# TDA7000.net
KiCad netlist of a schematic drawn in Altium Designer
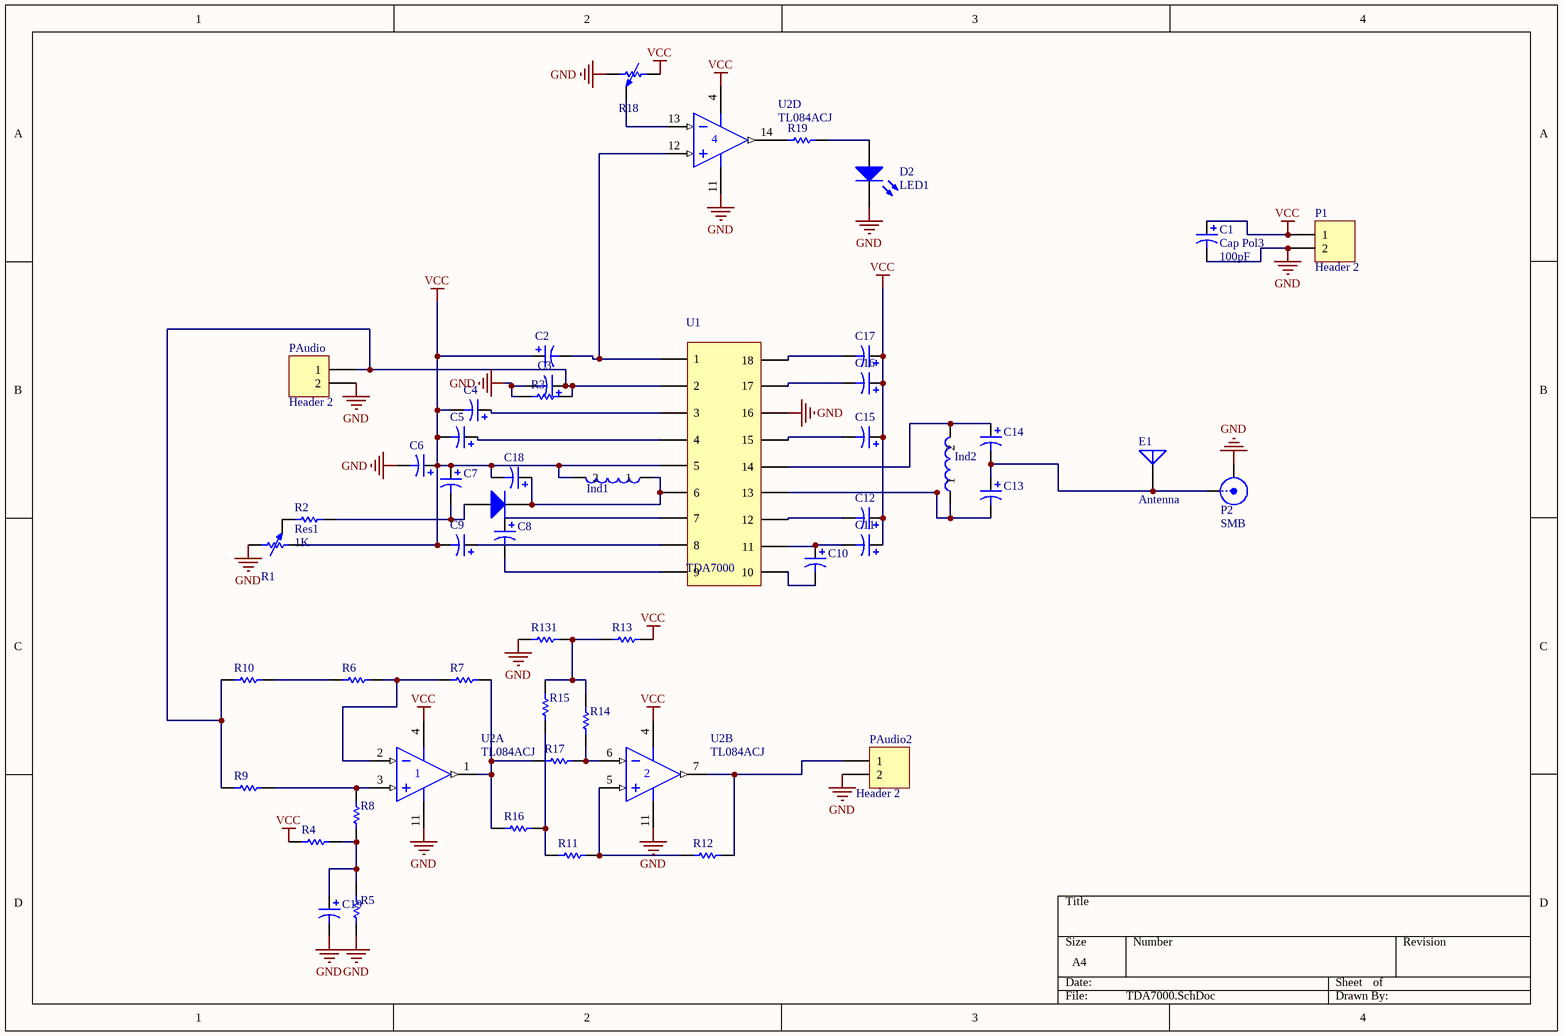
[diagram p0: TDA7000.SchDoc]

(export (version "E")
  (design (tool "Eeschema 10.0.6"))
  (components
    (comp (ref "C1")
      (value "Cap Pol3")
      (footprint "C0805")
      (description "Polarized Capacitor (Surface Mount)")
      (fields (field (name "ALTIUM_VALUE") "100pF") (field (name "PUBLISHER") "Altium Limited"))
      (libsource (lib "Miscellaneous Devices") (part "Cap Pol3"))
    )
    (comp (ref "C2")
      (value "Cap Pol3")
      (footprint "C0805")
      (description "Polarized Capacitor (Surface Mount)")
      (fields (field (name "PUBLISHER") "Altium Limited"))
      (libsource (lib "Miscellaneous Devices") (part "Cap Pol3"))
    )
    (comp (ref "C3")
      (value "Cap Pol3")
      (footprint "C0805")
      (description "Polarized Capacitor (Surface Mount)")
      (fields (field (name "PUBLISHER") "Altium Limited"))
      (libsource (lib "Miscellaneous Devices") (part "Cap Pol3"))
    )
    (comp (ref "C4")
      (value "Cap Pol3")
      (footprint "C0805")
      (description "Polarized Capacitor (Surface Mount)")
      (fields (field (name "PUBLISHER") "Altium Limited"))
      (libsource (lib "Miscellaneous Devices") (part "Cap Pol3"))
    )
    (comp (ref "C5")
      (value "Cap Pol3")
      (footprint "C0805")
      (description "Polarized Capacitor (Surface Mount)")
      (fields (field (name "PUBLISHER") "Altium Limited"))
      (libsource (lib "Miscellaneous Devices") (part "Cap Pol3"))
    )
    (comp (ref "C6")
      (value "Cap Pol3")
      (footprint "C0805")
      (description "Polarized Capacitor (Surface Mount)")
      (fields (field (name "PUBLISHER") "Altium Limited"))
      (libsource (lib "Miscellaneous Devices") (part "Cap Pol3"))
    )
    (comp (ref "C7")
      (value "Cap Pol3")
      (footprint "C0805")
      (description "Polarized Capacitor (Surface Mount)")
      (fields (field (name "PUBLISHER") "Altium Limited"))
      (libsource (lib "Miscellaneous Devices") (part "Cap Pol3"))
    )
    (comp (ref "C8")
      (value "Cap Pol3")
      (footprint "C0805")
      (description "Polarized Capacitor (Surface Mount)")
      (fields (field (name "PUBLISHER") "Altium Limited"))
      (libsource (lib "Miscellaneous Devices") (part "Cap Pol3"))
    )
    (comp (ref "C9")
      (value "Cap Pol3")
      (footprint "C0805")
      (description "Polarized Capacitor (Surface Mount)")
      (fields (field (name "PUBLISHER") "Altium Limited"))
      (libsource (lib "Miscellaneous Devices") (part "Cap Pol3"))
    )
    (comp (ref "C10")
      (value "Cap Pol3")
      (footprint "C0805")
      (description "Polarized Capacitor (Surface Mount)")
      (fields (field (name "PUBLISHER") "Altium Limited"))
      (libsource (lib "Miscellaneous Devices") (part "Cap Pol3"))
    )
    (comp (ref "C11")
      (value "Cap Pol3")
      (footprint "C0805")
      (description "Polarized Capacitor (Surface Mount)")
      (fields (field (name "PUBLISHER") "Altium Limited"))
      (libsource (lib "Miscellaneous Devices") (part "Cap Pol3"))
    )
    (comp (ref "C12")
      (value "Cap Pol3")
      (footprint "C0805")
      (description "Polarized Capacitor (Surface Mount)")
      (fields (field (name "PUBLISHER") "Altium Limited"))
      (libsource (lib "Miscellaneous Devices") (part "Cap Pol3"))
    )
    (comp (ref "C13")
      (value "Cap Pol3")
      (footprint "C0805")
      (description "Polarized Capacitor (Surface Mount)")
      (fields (field (name "PUBLISHER") "Altium Limited"))
      (libsource (lib "Miscellaneous Devices") (part "Cap Pol3"))
    )
    (comp (ref "C14")
      (value "Cap Pol3")
      (footprint "C0805")
      (description "Polarized Capacitor (Surface Mount)")
      (fields (field (name "PUBLISHER") "Altium Limited"))
      (libsource (lib "Miscellaneous Devices") (part "Cap Pol3"))
    )
    (comp (ref "C15")
      (value "Cap Pol3")
      (footprint "C0805")
      (description "Polarized Capacitor (Surface Mount)")
      (fields (field (name "PUBLISHER") "Altium Limited"))
      (libsource (lib "Miscellaneous Devices") (part "Cap Pol3"))
    )
    (comp (ref "C16")
      (value "Cap Pol3")
      (footprint "C0805")
      (description "Polarized Capacitor (Surface Mount)")
      (fields (field (name "PUBLISHER") "Altium Limited"))
      (libsource (lib "Miscellaneous Devices") (part "Cap Pol3"))
    )
    (comp (ref "C17")
      (value "Cap Pol3")
      (footprint "C0805")
      (description "Polarized Capacitor (Surface Mount)")
      (fields (field (name "PUBLISHER") "Altium Limited"))
      (libsource (lib "Miscellaneous Devices") (part "Cap Pol3"))
    )
    (comp (ref "C18")
      (value "Cap Pol3")
      (footprint "C0805")
      (description "Polarized Capacitor (Surface Mount)")
      (fields (field (name "PUBLISHER") "Altium Limited"))
      (libsource (lib "Miscellaneous Devices") (part "Cap Pol3"))
    )
    (comp (ref "C19")
      (value "Cap Pol3")
      (footprint "C0805")
      (description "Polarized Capacitor (Surface Mount)")
      (fields (field (name "PUBLISHER") "Altium Limited"))
      (libsource (lib "Miscellaneous Devices") (part "Cap Pol3"))
    )
    (comp (ref "D1")
      (value "Diode 1N914")
      (footprint "DO-35")
      (description "High Conductance Fast Diode")
      (fields (field (name "PUBLISHER") "Altium Limited"))
      (libsource (lib "Miscellaneous Devices") (part "Diode 1N914"))
    )
    (comp (ref "D2")
      (value "LED1")
      (footprint "LED-1")
      (description "Typical RED GaAs LED")
      (fields (field (name "PUBLISHER") "Altium Limited"))
      (libsource (lib "Miscellaneous Devices") (part "LED1"))
    )
    (comp (ref "E1")
      (value "Antenna")
      (footprint "PIN1")
      (description "Generic Antenna")
      (fields (field (name "PUBLISHER") "Altium Limited"))
      (libsource (lib "Miscellaneous Devices") (part "Antenna"))
    )
    (comp (ref "Ind1") (value "Ind2") (footprint "Ind_3mm") (libsource (lib "epf") (part "Ind2")))
    (comp (ref "Ind2") (value "Ind2") (footprint "Ind_3mm") (libsource (lib "epf") (part "Ind2")))
    (comp (ref "P1")
      (value "Header 2")
      (footprint "HDR1X2")
      (description "Header, 2-Pin")
      (fields (field (name "PUBLISHER") "Altium Limited"))
      (libsource (lib "") (part "Header 2_1"))
    )
    (comp (ref "P2")
      (value "SMB")
      (footprint "SMB_V-RJ45")
      (description "SMB Straight Connector")
      (fields (field (name "PUBLISHER") "Altium Limited"))
      (libsource (lib "Miscellaneous Connectors") (part "SMB"))
    )
    (comp (ref "PAudio")
      (value "Header 2")
      (footprint "HDR1X2")
      (description "Header, 2-Pin")
      (fields (field (name "PUBLISHER") "Altium Limited"))
      (libsource (lib "Miscellaneous Connectors") (part "Header 2"))
    )
    (comp (ref "PAudio2")
      (value "Header 2")
      (footprint "HDR1X2")
      (description "Header, 2-Pin")
      (fields (field (name "PUBLISHER") "Altium Limited"))
      (libsource (lib "") (part "Header 2_1"))
    )
    (comp (ref "R1") (value "Pot") (footprint "Potenciometro") (libsource (lib "epf") (part "Pot")))
    (comp (ref "R2")
      (value "Res1")
      (footprint "AXIAL-0.3")
      (description "Resistor")
      (fields (field (name "ALTIUM_VALUE") "1K") (field (name "PUBLISHER") "Altium Limited"))
      (libsource (lib "Miscellaneous Devices") (part "Res1"))
    )
    (comp (ref "R3")
      (value "Res Semi")
      (footprint "2012[0805]")
      (description "Semiconductor Resistor")
      (fields (field (name "PUBLISHER") "Altium Limited"))
      (libsource (lib "Miscellaneous Devices") (part "Res Semi"))
    )
    (comp (ref "R4")
      (value "Res Semi")
      (footprint "2012[0805]")
      (description "Semiconductor Resistor")
      (fields (field (name "PUBLISHER") "Altium Limited"))
      (libsource (lib "Miscellaneous Devices") (part "Res Semi"))
    )
    (comp (ref "R5")
      (value "Res Semi")
      (footprint "2012[0805]")
      (description "Semiconductor Resistor")
      (fields (field (name "PUBLISHER") "Altium Limited"))
      (libsource (lib "Miscellaneous Devices") (part "Res Semi"))
    )
    (comp (ref "R6")
      (value "Res Semi")
      (footprint "2012[0805]")
      (description "Semiconductor Resistor")
      (fields (field (name "PUBLISHER") "Altium Limited"))
      (libsource (lib "Miscellaneous Devices") (part "Res Semi"))
    )
    (comp (ref "R7")
      (value "Res Semi")
      (footprint "2012[0805]")
      (description "Semiconductor Resistor")
      (fields (field (name "PUBLISHER") "Altium Limited"))
      (libsource (lib "Miscellaneous Devices") (part "Res Semi"))
    )
    (comp (ref "R8")
      (value "Res Semi")
      (footprint "2012[0805]")
      (description "Semiconductor Resistor")
      (fields (field (name "PUBLISHER") "Altium Limited"))
      (libsource (lib "Miscellaneous Devices") (part "Res Semi"))
    )
    (comp (ref "R9")
      (value "Res Semi")
      (footprint "2012[0805]")
      (description "Semiconductor Resistor")
      (fields (field (name "PUBLISHER") "Altium Limited"))
      (libsource (lib "Miscellaneous Devices") (part "Res Semi"))
    )
    (comp (ref "R10")
      (value "Res Semi")
      (footprint "2012[0805]")
      (description "Semiconductor Resistor")
      (fields (field (name "PUBLISHER") "Altium Limited"))
      (libsource (lib "Miscellaneous Devices") (part "Res Semi"))
    )
    (comp (ref "R11")
      (value "Res Semi")
      (footprint "2012[0805]")
      (description "Semiconductor Resistor")
      (fields (field (name "PUBLISHER") "Altium Limited"))
      (libsource (lib "Miscellaneous Devices") (part "Res Semi"))
    )
    (comp (ref "R12")
      (value "Res Semi")
      (footprint "2012[0805]")
      (description "Semiconductor Resistor")
      (fields (field (name "PUBLISHER") "Altium Limited"))
      (libsource (lib "Miscellaneous Devices") (part "Res Semi"))
    )
    (comp (ref "R13")
      (value "Res Semi")
      (footprint "2012[0805]")
      (description "Semiconductor Resistor")
      (fields (field (name "PUBLISHER") "Altium Limited"))
      (libsource (lib "Miscellaneous Devices") (part "Res Semi"))
    )
    (comp (ref "R14")
      (value "Res Semi")
      (footprint "2012[0805]")
      (description "Semiconductor Resistor")
      (fields (field (name "PUBLISHER") "Altium Limited"))
      (libsource (lib "Miscellaneous Devices") (part "Res Semi"))
    )
    (comp (ref "R15")
      (value "Res Semi")
      (footprint "2012[0805]")
      (description "Semiconductor Resistor")
      (fields (field (name "PUBLISHER") "Altium Limited"))
      (libsource (lib "Miscellaneous Devices") (part "Res Semi"))
    )
    (comp (ref "R16")
      (value "Res Semi")
      (footprint "2012[0805]")
      (description "Semiconductor Resistor")
      (fields (field (name "PUBLISHER") "Altium Limited"))
      (libsource (lib "Miscellaneous Devices") (part "Res Semi"))
    )
    (comp (ref "R17")
      (value "Res Semi")
      (footprint "2012[0805]")
      (description "Semiconductor Resistor")
      (fields (field (name "PUBLISHER") "Altium Limited"))
      (libsource (lib "Miscellaneous Devices") (part "Res Semi"))
    )
    (comp (ref "R18") (value "Pot") (footprint "Potenciometro") (libsource (lib "epf") (part "Pot")))
    (comp (ref "R19")
      (value "Res Semi")
      (footprint "2012[0805]")
      (description "Semiconductor Resistor")
      (fields (field (name "PUBLISHER") "Altium Limited"))
      (libsource (lib "Miscellaneous Devices") (part "Res Semi"))
    )
    (comp (ref "R131")
      (value "Res Semi")
      (footprint "2012[0805]")
      (description "Semiconductor Resistor")
      (fields (field (name "PUBLISHER") "Altium Limited"))
      (libsource (lib "Miscellaneous Devices") (part "Res Semi"))
    )
    (comp (ref "U1") (value "TDA7000") (footprint "TDA7000") (libsource (lib "epf") (part "TDA7000")))
    (comp (ref "U2")
      (value "TL084ACJ")
      (footprint "632-08")
      (description "JFET-Input Operational Amplifier")
      (fields (field (name "PUBLISHER") "Altium Limited"))
      (libsource (lib "Motorola Amplifier Operational Amplifier") (part "TL084ACJ"))
    )
  )
  (nets
    (net (code "1") (name "GND") (class "Default")
      (node (ref "C1") (pin "2") (pinfunction "2_2") (pintype "passive"))
      (node (ref "C19") (pin "2") (pinfunction "2_2") (pintype "passive"))
      (node (ref "C3") (pin "2") (pinfunction "2_2") (pintype "passive"))
      (node (ref "C6") (pin "2") (pinfunction "2_2") (pintype "passive"))
      (node (ref "D2") (pin "2") (pinfunction "K_2") (pintype "passive"))
      (node (ref "P1") (pin "2") (pinfunction "2_2") (pintype "passive"))
      (node (ref "P2") (pin "2") (pinfunction "Y_2") (pintype "passive"))
      (node (ref "PAudio") (pin "2") (pinfunction "2_2") (pintype "passive"))
      (node (ref "PAudio2") (pin "2") (pinfunction "2_2") (pintype "passive"))
      (node (ref "R1") (pin "1") (pinfunction "1_1") (pintype "passive"))
      (node (ref "R131") (pin "2") (pinfunction "2_2") (pintype "passive"))
      (node (ref "R18") (pin "2") (pinfunction "2_2") (pintype "passive"))
      (node (ref "R3") (pin "1") (pinfunction "1_1") (pintype "passive"))
      (node (ref "R5") (pin "1") (pinfunction "1_1") (pintype "passive"))
      (node (ref "U1") (pin "16") (pinfunction "16_16") (pintype "passive"))
      (node (ref "U2") (pin "11") (pinfunction "V-_11") (pintype "power_in"))
    )
    (net (code "2") (name "Net-(C3-Pad1)") (class "Default")
      (node (ref "C3") (pin "1") (pinfunction "1_1") (pintype "passive"))
      (node (ref "PAudio") (pin "1") (pinfunction "1_1") (pintype "passive"))
      (node (ref "R10") (pin "2") (pinfunction "2_2") (pintype "passive"))
      (node (ref "R3") (pin "2") (pinfunction "2_2") (pintype "passive"))
      (node (ref "R9") (pin "2") (pinfunction "2_2") (pintype "passive"))
      (node (ref "U1") (pin "2") (pinfunction "2_2") (pintype "passive"))
    )
    (net (code "3") (name "Net-(C4-Pad1)") (class "Default")
      (node (ref "C4") (pin "1") (pinfunction "1_1") (pintype "passive"))
      (node (ref "U1") (pin "3") (pinfunction "3_3") (pintype "passive"))
    )
    (net (code "4") (name "Net-(C5-Pad1)") (class "Default")
      (node (ref "C5") (pin "1") (pinfunction "1_1") (pintype "passive"))
      (node (ref "U1") (pin "4") (pinfunction "4_4") (pintype "passive"))
    )
    (net (code "5") (name "Net-(C8-Pad1)") (class "Default")
      (node (ref "C8") (pin "1") (pinfunction "1_1") (pintype "passive"))
      (node (ref "U1") (pin "7") (pinfunction "7_7") (pintype "passive"))
    )
    (net (code "6") (name "Net-(C8-Pad2)") (class "Default")
      (node (ref "C8") (pin "2") (pinfunction "2_2") (pintype "passive"))
      (node (ref "U1") (pin "9") (pinfunction "9_9") (pintype "passive"))
    )
    (net (code "7") (name "Net-(C9-Pad1)") (class "Default")
      (node (ref "C9") (pin "1") (pinfunction "1_1") (pintype "passive"))
      (node (ref "U1") (pin "8") (pinfunction "8_8") (pintype "passive"))
    )
    (net (code "8") (name "Net-(C10-Pad1)") (class "Default")
      (node (ref "C10") (pin "1") (pinfunction "1_1") (pintype "passive"))
      (node (ref "C11") (pin "2") (pinfunction "2_2") (pintype "passive"))
      (node (ref "U1") (pin "11") (pinfunction "11_11") (pintype "passive"))
    )
    (net (code "9") (name "Net-(C10-Pad2)") (class "Default")
      (node (ref "C10") (pin "2") (pinfunction "2_2") (pintype "passive"))
      (node (ref "U1") (pin "10") (pinfunction "10_10") (pintype "passive"))
    )
    (net (code "10") (name "Net-(C12-Pad2)") (class "Default")
      (node (ref "C12") (pin "2") (pinfunction "2_2") (pintype "passive"))
      (node (ref "U1") (pin "12") (pinfunction "12_12") (pintype "passive"))
    )
    (net (code "11") (name "Net-(C13-Pad2)") (class "Default")
      (node (ref "C13") (pin "2") (pinfunction "2_2") (pintype "passive"))
      (node (ref "Ind2") (pin "1") (pinfunction "1_1") (pintype "passive"))
      (node (ref "U1") (pin "13") (pinfunction "13_13") (pintype "passive"))
    )
    (net (code "12") (name "Net-(C14-Pad1)") (class "Default")
      (node (ref "C14") (pin "1") (pinfunction "1_1") (pintype "passive"))
      (node (ref "Ind2") (pin "2") (pinfunction "2_2") (pintype "passive"))
      (node (ref "U1") (pin "14") (pinfunction "14_14") (pintype "passive"))
    )
    (net (code "13") (name "Net-(C15-Pad2)") (class "Default")
      (node (ref "C15") (pin "2") (pinfunction "2_2") (pintype "passive"))
      (node (ref "U1") (pin "15") (pinfunction "15_15") (pintype "passive"))
    )
    (net (code "14") (name "Net-(C16-Pad2)") (class "Default")
      (node (ref "C16") (pin "2") (pinfunction "2_2") (pintype "passive"))
      (node (ref "U1") (pin "17") (pinfunction "17_17") (pintype "passive"))
    )
    (net (code "15") (name "Net-(C17-Pad2)") (class "Default")
      (node (ref "C17") (pin "2") (pinfunction "2_2") (pintype "passive"))
      (node (ref "U1") (pin "18") (pinfunction "18_18") (pintype "passive"))
    )
    (net (code "16") (name "Net-(C19-Pad1)") (class "Default")
      (node (ref "C19") (pin "1") (pinfunction "1_1") (pintype "passive"))
      (node (ref "R4") (pin "2") (pinfunction "2_2") (pintype "passive"))
      (node (ref "R5") (pin "2") (pinfunction "2_2") (pintype "passive"))
      (node (ref "R8") (pin "1") (pinfunction "1_1") (pintype "passive"))
    )
    (net (code "17") (name "Net-(D1-A)") (class "Default")
      (node (ref "C7") (pin "2") (pinfunction "2_2") (pintype "passive"))
      (node (ref "D1") (pin "1") (pinfunction "A_1") (pintype "passive"))
      (node (ref "R2") (pin "2") (pinfunction "2_2") (pintype "passive"))
    )
    (net (code "18") (name "Net-(D1-K)") (class "Default")
      (node (ref "C18") (pin "1") (pinfunction "1_1") (pintype "passive"))
      (node (ref "D1") (pin "2") (pinfunction "K_2") (pintype "passive"))
      (node (ref "Ind1") (pin "1") (pinfunction "1_1") (pintype "passive"))
      (node (ref "U1") (pin "6") (pinfunction "6_6") (pintype "passive"))
    )
    (net (code "19") (name "Net-(D2-A)") (class "Default")
      (node (ref "D2") (pin "1") (pinfunction "A_1") (pintype "passive"))
      (node (ref "R19") (pin "2") (pinfunction "2_2") (pintype "passive"))
    )
    (net (code "20") (name "Net-(E1-A)") (class "Default")
      (node (ref "C13") (pin "1") (pinfunction "1_1") (pintype "passive"))
      (node (ref "C14") (pin "2") (pinfunction "2_2") (pintype "passive"))
      (node (ref "E1") (pin "1") (pinfunction "A_1") (pintype "passive"))
      (node (ref "P2") (pin "1") (pinfunction "X_1") (pintype "passive"))
    )
    (net (code "21") (name "Net-(R1-Pad3)") (class "Default")
      (node (ref "R1") (pin "3") (pinfunction "3_3") (pintype "passive"))
      (node (ref "R2") (pin "1") (pinfunction "1_1") (pintype "passive"))
    )
    (net (code "22") (name "Net-(R10-Pad1)") (class "Default")
      (node (ref "R10") (pin "1") (pinfunction "1_1") (pintype "passive"))
      (node (ref "R6") (pin "2") (pinfunction "2_2") (pintype "passive"))
    )
    (net (code "23") (name "Net-(R11-Pad2)") (class "Default")
      (node (ref "R11") (pin "2") (pinfunction "2_2") (pintype "passive"))
      (node (ref "R15") (pin "2") (pinfunction "2_2") (pintype "passive"))
      (node (ref "R16") (pin "2") (pinfunction "2_2") (pintype "passive"))
    )
    (net (code "24") (name "Net-(R13-Pad2)") (class "Default")
      (node (ref "R13") (pin "2") (pinfunction "2_2") (pintype "passive"))
      (node (ref "R131") (pin "1") (pinfunction "1_1") (pintype "passive"))
      (node (ref "R14") (pin "1") (pinfunction "1_1") (pintype "passive"))
      (node (ref "R15") (pin "1") (pinfunction "1_1") (pintype "passive"))
    )
    (net (code "25") (name "Net-(U2A-IN+)") (class "Default")
      (node (ref "R8") (pin "2") (pinfunction "2_2") (pintype "passive"))
      (node (ref "R9") (pin "1") (pinfunction "1_1") (pintype "passive"))
      (node (ref "U2") (pin "3") (pinfunction "IN+_3") (pintype "input"))
    )
    (net (code "26") (name "Net-(U2A-IN-)") (class "Default")
      (node (ref "R6") (pin "1") (pinfunction "1_1") (pintype "passive"))
      (node (ref "R7") (pin "2") (pinfunction "2_2") (pintype "passive"))
      (node (ref "U2") (pin "2") (pinfunction "IN-_2") (pintype "input"))
    )
    (net (code "27") (name "Net-(U2A-OUT)") (class "Default")
      (node (ref "R16") (pin "1") (pinfunction "1_1") (pintype "passive"))
      (node (ref "R17") (pin "1") (pinfunction "1_1") (pintype "passive"))
      (node (ref "R7") (pin "1") (pinfunction "1_1") (pintype "passive"))
      (node (ref "U2") (pin "1") (pinfunction "OUT_1") (pintype "output"))
    )
    (net (code "28") (name "Net-(U2B-IN+)") (class "Default")
      (node (ref "R11") (pin "1") (pinfunction "1_1") (pintype "passive"))
      (node (ref "R12") (pin "2") (pinfunction "2_2") (pintype "passive"))
      (node (ref "U2") (pin "5") (pinfunction "IN+_5") (pintype "input"))
    )
    (net (code "29") (name "Net-(U2B-IN-)") (class "Default")
      (node (ref "R14") (pin "2") (pinfunction "2_2") (pintype "passive"))
      (node (ref "R17") (pin "2") (pinfunction "2_2") (pintype "passive"))
      (node (ref "U2") (pin "6") (pinfunction "IN-_6") (pintype "input"))
    )
    (net (code "30") (name "Net-(U2B-OUT)") (class "Default")
      (node (ref "PAudio2") (pin "1") (pinfunction "1_1") (pintype "passive"))
      (node (ref "R12") (pin "1") (pinfunction "1_1") (pintype "passive"))
      (node (ref "U2") (pin "7") (pinfunction "OUT_7") (pintype "output"))
    )
    (net (code "31") (name "Net-(U2D-IN+)") (class "Default")
      (node (ref "C2") (pin "2") (pinfunction "2_2") (pintype "passive"))
      (node (ref "U1") (pin "1") (pinfunction "1_1") (pintype "passive"))
      (node (ref "U2") (pin "12") (pinfunction "IN+_12") (pintype "input"))
    )
    (net (code "32") (name "Net-(U2D-IN-)") (class "Default")
      (node (ref "R18") (pin "3") (pinfunction "3_3") (pintype "passive"))
      (node (ref "U2") (pin "13") (pinfunction "IN-_13") (pintype "input"))
    )
    (net (code "33") (name "Net-(U2D-OUT)") (class "Default")
      (node (ref "R19") (pin "1") (pinfunction "1_1") (pintype "passive"))
      (node (ref "U2") (pin "14") (pinfunction "OUT_14") (pintype "output"))
    )
    (net (code "34") (name "VCC") (class "Default")
      (node (ref "C1") (pin "1") (pinfunction "1_1") (pintype "passive"))
      (node (ref "C11") (pin "1") (pinfunction "1_1") (pintype "passive"))
      (node (ref "C12") (pin "1") (pinfunction "1_1") (pintype "passive"))
      (node (ref "C15") (pin "1") (pinfunction "1_1") (pintype "passive"))
      (node (ref "C16") (pin "1") (pinfunction "1_1") (pintype "passive"))
      (node (ref "C17") (pin "1") (pinfunction "1_1") (pintype "passive"))
      (node (ref "C18") (pin "2") (pinfunction "2_2") (pintype "passive"))
      (node (ref "C2") (pin "1") (pinfunction "1_1") (pintype "passive"))
      (node (ref "C4") (pin "2") (pinfunction "2_2") (pintype "passive"))
      (node (ref "C5") (pin "2") (pinfunction "2_2") (pintype "passive"))
      (node (ref "C6") (pin "1") (pinfunction "1_1") (pintype "passive"))
      (node (ref "C7") (pin "1") (pinfunction "1_1") (pintype "passive"))
      (node (ref "C9") (pin "2") (pinfunction "2_2") (pintype "passive"))
      (node (ref "Ind1") (pin "2") (pinfunction "2_2") (pintype "passive"))
      (node (ref "P1") (pin "1") (pinfunction "1_1") (pintype "passive"))
      (node (ref "R1") (pin "2") (pinfunction "2_2") (pintype "passive"))
      (node (ref "R13") (pin "1") (pinfunction "1_1") (pintype "passive"))
      (node (ref "R18") (pin "1") (pinfunction "1_1") (pintype "passive"))
      (node (ref "R4") (pin "1") (pinfunction "1_1") (pintype "passive"))
      (node (ref "U1") (pin "5") (pinfunction "5_5") (pintype "passive"))
      (node (ref "U2") (pin "4") (pinfunction "V+_4") (pintype "power_in"))
    )
  )
)
